# turntable-vu-meters.net
KiCad netlist of a schematic drawn in EAGLE
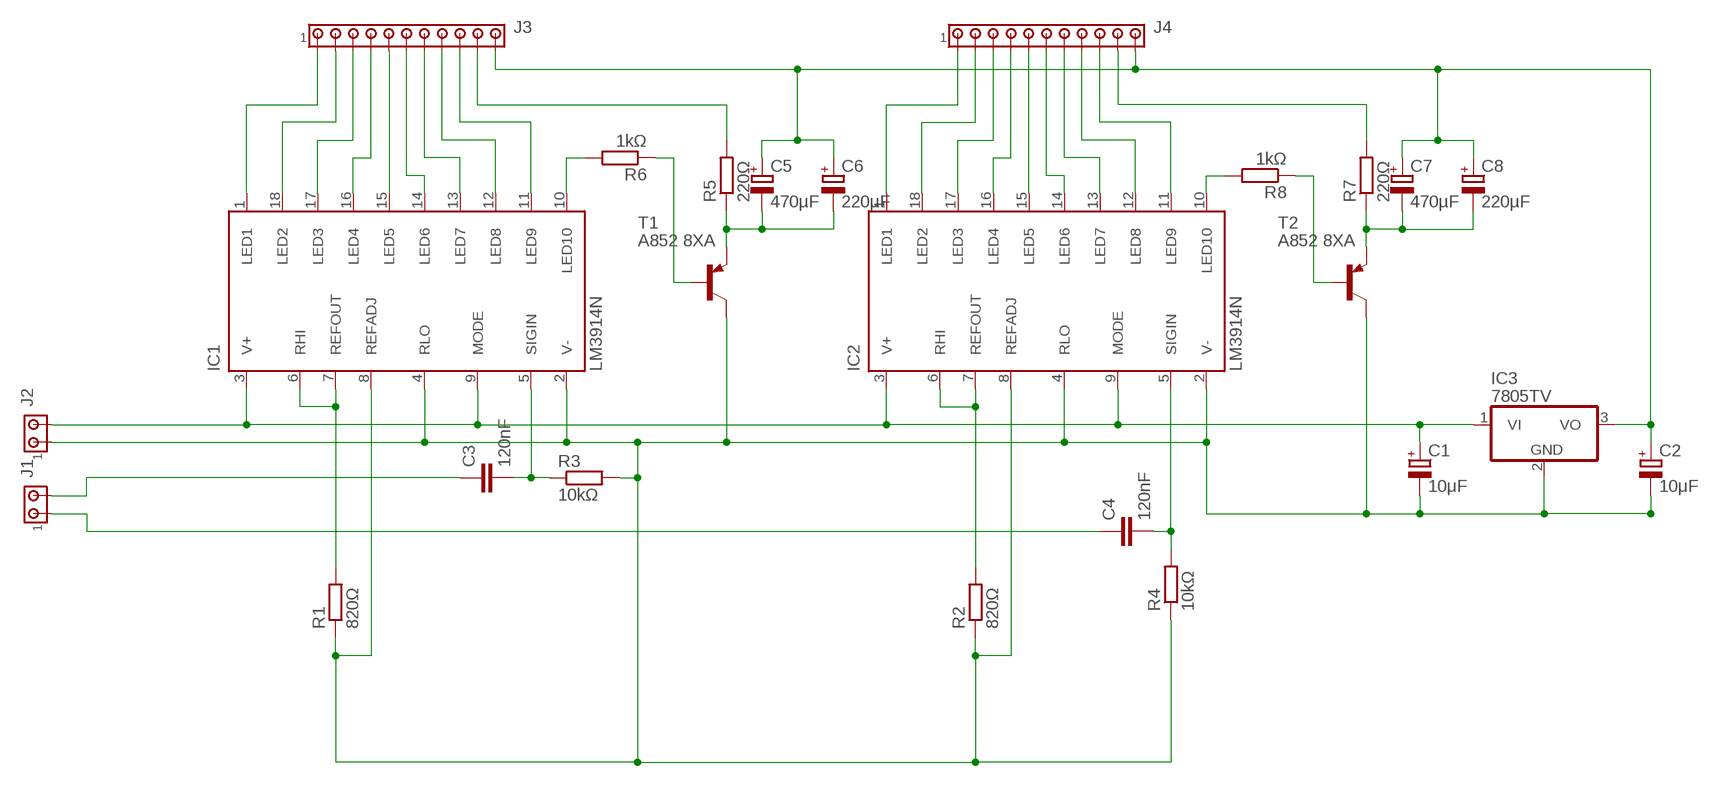
[diagram p0: schematic, sheet 1]

(export (version "E")
  (design (tool "Eeschema 10.0.6"))
  (components
    (comp (ref "C1")
      (value "10μF")
      (footprint "eagle-import:E5-6")
      (libsource (lib "eagle-import") (part "CPOL-EUE5-6"))
    )
    (comp (ref "C2")
      (value "10μF")
      (footprint "eagle-import:E5-6")
      (libsource (lib "eagle-import") (part "CPOL-EUE5-6"))
    )
    (comp (ref "C3")
      (value "120nF")
      (footprint "eagle-import:C075-052X106")
      (libsource (lib "eagle-import") (part "C-EU075-052X106"))
    )
    (comp (ref "C4")
      (value "120nF")
      (footprint "eagle-import:C075-052X106")
      (libsource (lib "eagle-import") (part "C-EU075-052X106"))
    )
    (comp (ref "C5")
      (value "470µF")
      (footprint "eagle-import:E3,5-8")
      (libsource (lib "eagle-import") (part "CPOL-EUE3.5-8"))
    )
    (comp (ref "C6")
      (value "220µF")
      (footprint "eagle-import:E2,5-7")
      (libsource (lib "eagle-import") (part "CPOL-EUE2.5-7"))
    )
    (comp (ref "C7")
      (value "470µF")
      (footprint "eagle-import:E3,5-8")
      (libsource (lib "eagle-import") (part "CPOL-EUE3.5-8"))
    )
    (comp (ref "C8")
      (value "220µF")
      (footprint "eagle-import:E2,5-7")
      (libsource (lib "eagle-import") (part "CPOL-EUE2.5-7"))
    )
    (comp (ref "IC1")
      (value "LM3914N")
      (footprint "eagle-import:DIL18")
      (libsource (lib "eagle-import") (part "LM391N4"))
    )
    (comp (ref "IC2")
      (value "LM3914N")
      (footprint "eagle-import:DIL18")
      (libsource (lib "eagle-import") (part "LM391N4"))
    )
    (comp (ref "IC3")
      (value "7805TV")
      (footprint "eagle-import:TO220V")
      (libsource (lib "eagle-import") (part "78TV05"))
    )
    (comp (ref "J1")
      (value "MTA02-156")
      (footprint "eagle-import:1X2MTA")
      (libsource (lib "eagle-import") (part "MTA02-156"))
    )
    (comp (ref "J2")
      (value "MTA02-156")
      (footprint "eagle-import:1X2MTA")
      (libsource (lib "eagle-import") (part "MTA02-156"))
    )
    (comp (ref "J3")
      (value "MTA11-156")
      (footprint "eagle-import:1X11MTA")
      (libsource (lib "eagle-import") (part "MTA11-156"))
    )
    (comp (ref "J4")
      (value "MTA11-156")
      (footprint "eagle-import:1X11MTA")
      (libsource (lib "eagle-import") (part "MTA11-156"))
    )
    (comp (ref "R1")
      (value "820Ω")
      (footprint "eagle-import:0204_7")
      (libsource (lib "eagle-import") (part "R-EU_0204/7"))
    )
    (comp (ref "R2")
      (value "820Ω")
      (footprint "eagle-import:0204_7")
      (libsource (lib "eagle-import") (part "R-EU_0204/7"))
    )
    (comp (ref "R3")
      (value "10kΩ")
      (footprint "eagle-import:0204_7")
      (libsource (lib "eagle-import") (part "R-EU_0204/7"))
    )
    (comp (ref "R4")
      (value "10kΩ")
      (footprint "eagle-import:0204_7")
      (libsource (lib "eagle-import") (part "R-EU_0204/7"))
    )
    (comp (ref "R5")
      (value "220Ω")
      (footprint "eagle-import:0204_7")
      (libsource (lib "eagle-import") (part "R-EU_0204/7"))
    )
    (comp (ref "R6")
      (value "1kΩ")
      (footprint "eagle-import:0204_7")
      (libsource (lib "eagle-import") (part "R-EU_0204/7"))
    )
    (comp (ref "R7")
      (value "220Ω")
      (footprint "eagle-import:0204_7")
      (libsource (lib "eagle-import") (part "R-EU_0204/7"))
    )
    (comp (ref "R8")
      (value "1kΩ")
      (footprint "eagle-import:0204_7")
      (libsource (lib "eagle-import") (part "R-EU_0204/7"))
    )
    (comp (ref "T1")
      (value "A852 8XA")
      (footprint "eagle-import:TO92")
      (libsource (lib "eagle-import") (part "-PNP-TO92"))
    )
    (comp (ref "T2")
      (value "A852 8XA")
      (footprint "eagle-import:TO92")
      (libsource (lib "eagle-import") (part "-PNP-TO92"))
    )
  )
  (nets
    (net (code "1") (name "Net-(C3-Pad1)") (class "Default")
      (node (ref "C3") (pin "1") (pinfunction "1_1") (pintype "passive"))
      (node (ref "J1") (pin "2") (pinfunction "2_2") (pintype "passive"))
    )
    (net (code "2") (name "Net-(C4-Pad1)") (class "Default")
      (node (ref "C4") (pin "1") (pinfunction "1_1") (pintype "passive"))
      (node (ref "J1") (pin "1") (pinfunction "1_1") (pintype "passive"))
    )
    (net (code "3") (name "Net-(IC1-LED1)") (class "Default")
      (node (ref "IC1") (pin "1") (pinfunction "LED1_1") (pintype "output"))
      (node (ref "J3") (pin "1") (pinfunction "1_1") (pintype "passive"))
    )
    (net (code "4") (name "Net-(IC1-LED2)") (class "Default")
      (node (ref "IC1") (pin "18") (pinfunction "LED2_18") (pintype "output"))
      (node (ref "J3") (pin "2") (pinfunction "2_2") (pintype "passive"))
    )
    (net (code "5") (name "Net-(IC1-LED3)") (class "Default")
      (node (ref "IC1") (pin "17") (pinfunction "LED3_17") (pintype "output"))
      (node (ref "J3") (pin "3") (pinfunction "3_3") (pintype "passive"))
    )
    (net (code "6") (name "Net-(IC1-LED4)") (class "Default")
      (node (ref "IC1") (pin "16") (pinfunction "LED4_16") (pintype "output"))
      (node (ref "J3") (pin "4") (pinfunction "4_4") (pintype "passive"))
    )
    (net (code "7") (name "Net-(IC1-LED5)") (class "Default")
      (node (ref "IC1") (pin "15") (pinfunction "LED5_15") (pintype "output"))
      (node (ref "J3") (pin "5") (pinfunction "5_5") (pintype "passive"))
    )
    (net (code "8") (name "Net-(IC1-LED6)") (class "Default")
      (node (ref "IC1") (pin "14") (pinfunction "LED6_14") (pintype "output"))
      (node (ref "J3") (pin "6") (pinfunction "6_6") (pintype "passive"))
    )
    (net (code "9") (name "Net-(IC1-LED7)") (class "Default")
      (node (ref "IC1") (pin "13") (pinfunction "LED7_13") (pintype "output"))
      (node (ref "J3") (pin "7") (pinfunction "7_7") (pintype "passive"))
    )
    (net (code "10") (name "Net-(IC1-LED8)") (class "Default")
      (node (ref "IC1") (pin "12") (pinfunction "LED8_12") (pintype "output"))
      (node (ref "J3") (pin "8") (pinfunction "8_8") (pintype "passive"))
    )
    (net (code "11") (name "Net-(IC1-LED9)") (class "Default")
      (node (ref "IC1") (pin "11") (pinfunction "LED9_11") (pintype "output"))
      (node (ref "J3") (pin "9") (pinfunction "9_9") (pintype "passive"))
    )
    (net (code "12") (name "Net-(IC1-LED10)") (class "Default")
      (node (ref "IC1") (pin "10") (pinfunction "LED10_10") (pintype "output"))
      (node (ref "R6") (pin "2") (pinfunction "2_2") (pintype "passive"))
    )
    (net (code "13") (name "Net-(IC1-MODE)") (class "Default")
      (node (ref "C1") (pin "+") (pinfunction "+_+") (pintype "passive"))
      (node (ref "IC1") (pin "3") (pinfunction "V+_3") (pintype "power_in"))
      (node (ref "IC1") (pin "9") (pinfunction "MODE_9") (pintype "input"))
      (node (ref "IC2") (pin "3") (pinfunction "V+_3") (pintype "power_in"))
      (node (ref "IC2") (pin "9") (pinfunction "MODE_9") (pintype "input"))
      (node (ref "IC3") (pin "1") (pinfunction "VI_1") (pintype "input"))
      (node (ref "J2") (pin "2") (pinfunction "2_2") (pintype "passive"))
    )
    (net (code "14") (name "Net-(IC1-REFADJ)") (class "Default")
      (node (ref "C1") (pin "-") (pinfunction "-_-") (pintype "passive"))
      (node (ref "C2") (pin "-") (pinfunction "-_-") (pintype "passive"))
      (node (ref "IC1") (pin "2") (pinfunction "V-_2") (pintype "power_in"))
      (node (ref "IC1") (pin "4") (pinfunction "RLO_4") (pintype "input"))
      (node (ref "IC1") (pin "8") (pinfunction "REFADJ_8") (pintype "passive"))
      (node (ref "IC2") (pin "2") (pinfunction "V-_2") (pintype "power_in"))
      (node (ref "IC2") (pin "4") (pinfunction "RLO_4") (pintype "input"))
      (node (ref "IC2") (pin "8") (pinfunction "REFADJ_8") (pintype "passive"))
      (node (ref "IC3") (pin "2") (pinfunction "GND_2") (pintype "passive"))
      (node (ref "J2") (pin "1") (pinfunction "1_1") (pintype "passive"))
      (node (ref "R1") (pin "1") (pinfunction "1_1") (pintype "passive"))
      (node (ref "R2") (pin "1") (pinfunction "1_1") (pintype "passive"))
      (node (ref "R3") (pin "2") (pinfunction "2_2") (pintype "passive"))
      (node (ref "R4") (pin "1") (pinfunction "1_1") (pintype "passive"))
      (node (ref "T1") (pin "3") (pinfunction "C_3") (pintype "passive"))
      (node (ref "T2") (pin "3") (pinfunction "C_3") (pintype "passive"))
    )
    (net (code "15") (name "Net-(IC1-REFOUT)") (class "Default")
      (node (ref "IC1") (pin "6") (pinfunction "RHI_6") (pintype "input"))
      (node (ref "IC1") (pin "7") (pinfunction "REFOUT_7") (pintype "output"))
      (node (ref "R1") (pin "2") (pinfunction "2_2") (pintype "passive"))
    )
    (net (code "16") (name "Net-(IC1-SIGIN)") (class "Default")
      (node (ref "C3") (pin "2") (pinfunction "2_2") (pintype "passive"))
      (node (ref "IC1") (pin "5") (pinfunction "SIGIN_5") (pintype "input"))
      (node (ref "R3") (pin "1") (pinfunction "1_1") (pintype "passive"))
    )
    (net (code "17") (name "Net-(IC2-LED1)") (class "Default")
      (node (ref "IC2") (pin "1") (pinfunction "LED1_1") (pintype "output"))
      (node (ref "J4") (pin "1") (pinfunction "1_1") (pintype "passive"))
    )
    (net (code "18") (name "Net-(IC2-LED2)") (class "Default")
      (node (ref "IC2") (pin "18") (pinfunction "LED2_18") (pintype "output"))
      (node (ref "J4") (pin "2") (pinfunction "2_2") (pintype "passive"))
    )
    (net (code "19") (name "Net-(IC2-LED3)") (class "Default")
      (node (ref "IC2") (pin "17") (pinfunction "LED3_17") (pintype "output"))
      (node (ref "J4") (pin "3") (pinfunction "3_3") (pintype "passive"))
    )
    (net (code "20") (name "Net-(IC2-LED4)") (class "Default")
      (node (ref "IC2") (pin "16") (pinfunction "LED4_16") (pintype "output"))
      (node (ref "J4") (pin "4") (pinfunction "4_4") (pintype "passive"))
    )
    (net (code "21") (name "Net-(IC2-LED5)") (class "Default")
      (node (ref "IC2") (pin "15") (pinfunction "LED5_15") (pintype "output"))
      (node (ref "J4") (pin "5") (pinfunction "5_5") (pintype "passive"))
    )
    (net (code "22") (name "Net-(IC2-LED6)") (class "Default")
      (node (ref "IC2") (pin "14") (pinfunction "LED6_14") (pintype "output"))
      (node (ref "J4") (pin "6") (pinfunction "6_6") (pintype "passive"))
    )
    (net (code "23") (name "Net-(IC2-LED7)") (class "Default")
      (node (ref "IC2") (pin "13") (pinfunction "LED7_13") (pintype "output"))
      (node (ref "J4") (pin "7") (pinfunction "7_7") (pintype "passive"))
    )
    (net (code "24") (name "Net-(IC2-LED8)") (class "Default")
      (node (ref "IC2") (pin "12") (pinfunction "LED8_12") (pintype "output"))
      (node (ref "J4") (pin "8") (pinfunction "8_8") (pintype "passive"))
    )
    (net (code "25") (name "Net-(IC2-LED9)") (class "Default")
      (node (ref "IC2") (pin "11") (pinfunction "LED9_11") (pintype "output"))
      (node (ref "J4") (pin "9") (pinfunction "9_9") (pintype "passive"))
    )
    (net (code "26") (name "Net-(IC2-LED10)") (class "Default")
      (node (ref "IC2") (pin "10") (pinfunction "LED10_10") (pintype "output"))
      (node (ref "R8") (pin "2") (pinfunction "2_2") (pintype "passive"))
    )
    (net (code "27") (name "Net-(IC2-REFOUT)") (class "Default")
      (node (ref "IC2") (pin "6") (pinfunction "RHI_6") (pintype "input"))
      (node (ref "IC2") (pin "7") (pinfunction "REFOUT_7") (pintype "output"))
      (node (ref "R2") (pin "2") (pinfunction "2_2") (pintype "passive"))
    )
    (net (code "28") (name "Net-(IC2-SIGIN)") (class "Default")
      (node (ref "C4") (pin "2") (pinfunction "2_2") (pintype "passive"))
      (node (ref "IC2") (pin "5") (pinfunction "SIGIN_5") (pintype "input"))
      (node (ref "R4") (pin "2") (pinfunction "2_2") (pintype "passive"))
    )
    (net (code "29") (name "Net-(IC3-VO)") (class "Default")
      (node (ref "C2") (pin "+") (pinfunction "+_+") (pintype "passive"))
      (node (ref "C5") (pin "+") (pinfunction "+_+") (pintype "passive"))
      (node (ref "C6") (pin "+") (pinfunction "+_+") (pintype "passive"))
      (node (ref "C7") (pin "+") (pinfunction "+_+") (pintype "passive"))
      (node (ref "C8") (pin "+") (pinfunction "+_+") (pintype "passive"))
      (node (ref "IC3") (pin "3") (pinfunction "VO_3") (pintype "passive"))
      (node (ref "J3") (pin "11") (pinfunction "11_11") (pintype "passive"))
      (node (ref "J4") (pin "11") (pinfunction "11_11") (pintype "passive"))
    )
    (net (code "30") (name "Net-(J3-Pad10)") (class "Default")
      (node (ref "J3") (pin "10") (pinfunction "10_10") (pintype "passive"))
      (node (ref "R5") (pin "2") (pinfunction "2_2") (pintype "passive"))
    )
    (net (code "31") (name "Net-(J4-Pad10)") (class "Default")
      (node (ref "J4") (pin "10") (pinfunction "10_10") (pintype "passive"))
      (node (ref "R7") (pin "2") (pinfunction "2_2") (pintype "passive"))
    )
    (net (code "32") (name "Net-(T1-B)") (class "Default")
      (node (ref "R6") (pin "1") (pinfunction "1_1") (pintype "passive"))
      (node (ref "T1") (pin "2") (pinfunction "B_2") (pintype "passive"))
    )
    (net (code "33") (name "Net-(T1-E)") (class "Default")
      (node (ref "C5") (pin "-") (pinfunction "-_-") (pintype "passive"))
      (node (ref "C6") (pin "-") (pinfunction "-_-") (pintype "passive"))
      (node (ref "R5") (pin "1") (pinfunction "1_1") (pintype "passive"))
      (node (ref "T1") (pin "1") (pinfunction "E_1") (pintype "passive"))
    )
    (net (code "34") (name "Net-(T2-B)") (class "Default")
      (node (ref "R8") (pin "1") (pinfunction "1_1") (pintype "passive"))
      (node (ref "T2") (pin "2") (pinfunction "B_2") (pintype "passive"))
    )
    (net (code "35") (name "Net-(T2-E)") (class "Default")
      (node (ref "C7") (pin "-") (pinfunction "-_-") (pintype "passive"))
      (node (ref "C8") (pin "-") (pinfunction "-_-") (pintype "passive"))
      (node (ref "R7") (pin "1") (pinfunction "1_1") (pintype "passive"))
      (node (ref "T2") (pin "1") (pinfunction "E_1") (pintype "passive"))
    )
  )
)
